# MAX30100_Adapter.net
KiCad netlist of a schematic drawn in EAGLE
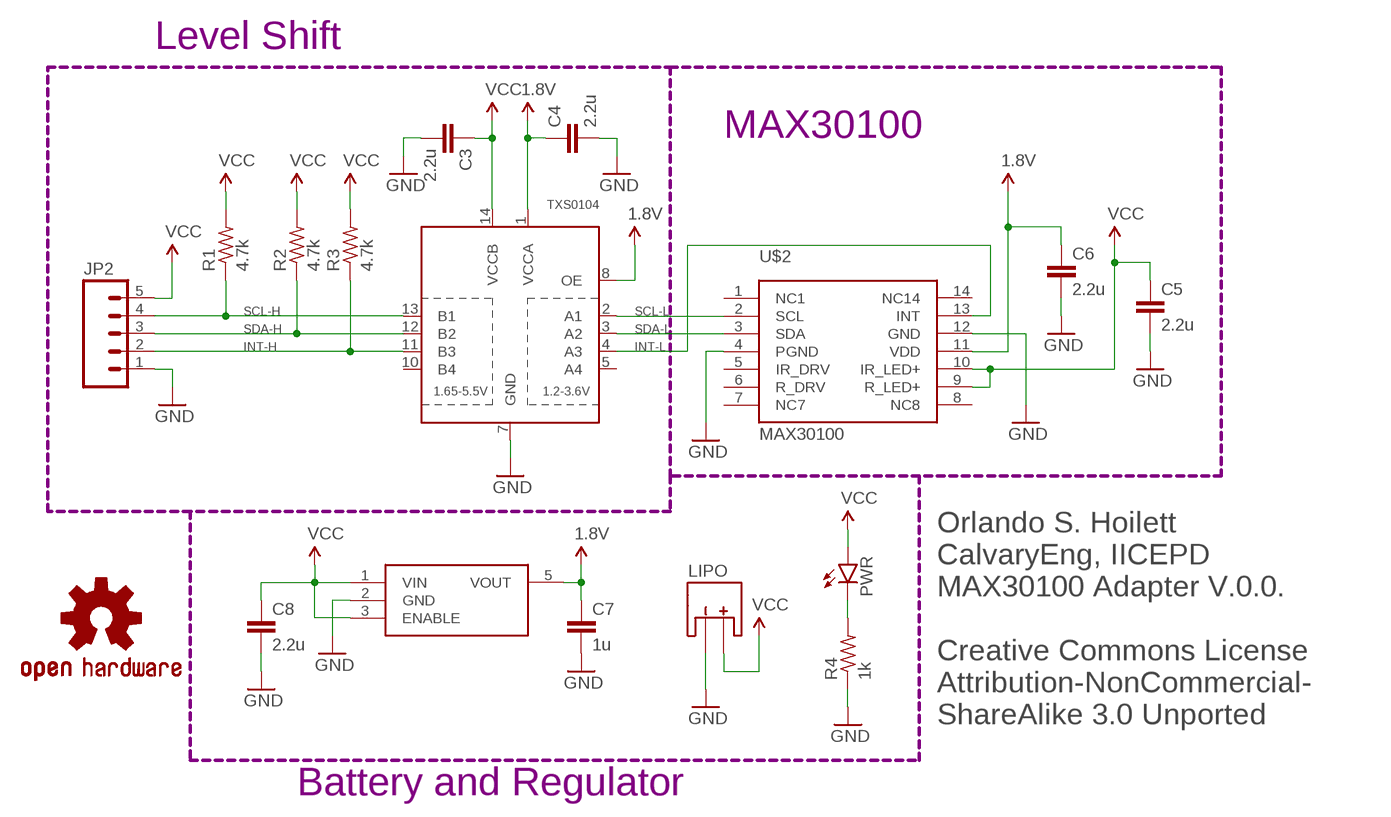
[diagram p0: schematic, sheet 1]

(export (version "E")
  (design (tool "Eeschema 10.0.6"))
  (components
    (comp (ref "C3")
      (value "2.2u")
      (footprint "eagle-import:C0402")
      (libsource (lib "eagle-import") (part "C-EUC0402"))
    )
    (comp (ref "C4")
      (value "2.2u")
      (footprint "eagle-import:C0402")
      (libsource (lib "eagle-import") (part "C-EUC0402"))
    )
    (comp (ref "C5")
      (value "2.2u")
      (footprint "eagle-import:C0402")
      (libsource (lib "eagle-import") (part "C-EUC0402"))
    )
    (comp (ref "C6")
      (value "2.2u")
      (footprint "eagle-import:C0402")
      (libsource (lib "eagle-import") (part "C-EUC0402"))
    )
    (comp (ref "C7")
      (value "1u")
      (footprint "eagle-import:C0402")
      (libsource (lib "eagle-import") (part "C-EUC0402"))
    )
    (comp (ref "C8")
      (value "2.2u")
      (footprint "eagle-import:C0402")
      (libsource (lib "eagle-import") (part "C-EUC0402"))
    )
    (comp (ref "JP2")
      (value "M05NO_SILK")
      (footprint "eagle-import:1X05_NO_SILK")
      (libsource (lib "eagle-import") (part "M05NO_SILK"))
    )
    (comp (ref "LDO")
      (value "MIC5504")
      (footprint "eagle-import:SOT23-5")
      (libsource (lib "eagle-import") (part "MIC5504"))
    )
    (comp (ref "LIPO")
      (value "JST-PTH")
      (footprint "eagle-import:JST-2-PTH-VERT")
      (libsource (lib "eagle-import") (part "JST-PTH"))
    )
    (comp (ref "LOGO1")
      (value "OSHW-LOGOS")
      (footprint "eagle-import:OSHW-LOGO-S")
      (libsource (lib "eagle-import") (part "OSHW-LOGOS"))
    )
    (comp (ref "PWR")
      (value "LED0603")
      (footprint "eagle-import:LED-0603")
      (libsource (lib "eagle-import") (part "LED0603"))
    )
    (comp (ref "R1")
      (value "4.7k")
      (footprint "eagle-import:R0402")
      (libsource (lib "eagle-import") (part "R-US_R0402"))
    )
    (comp (ref "R2")
      (value "4.7k")
      (footprint "eagle-import:R0402")
      (libsource (lib "eagle-import") (part "R-US_R0402"))
    )
    (comp (ref "R3")
      (value "4.7k")
      (footprint "eagle-import:R0402")
      (libsource (lib "eagle-import") (part "R-US_R0402"))
    )
    (comp (ref "R4")
      (value "1k")
      (footprint "eagle-import:R0402")
      (libsource (lib "eagle-import") (part "R-US_R0402"))
    )
    (comp (ref "TXS0104")
      (value "TXB0104PWR")
      (footprint "eagle-import:TSSOP14")
      (libsource (lib "eagle-import") (part "TXB0104PWR"))
    )
    (comp (ref "U$2")
      (value "MAX30100")
      (footprint "eagle-import:OESIP14")
      (libsource (lib "eagle-import") (part "MAX30100"))
    )
  )
  (nets
    (net (code "1") (name "/INT-H") (class "Default")
      (node (ref "JP2") (pin "2") (pinfunction "2_2") (pintype "passive"))
      (node (ref "R3") (pin "1") (pinfunction "1_1") (pintype "passive"))
      (node (ref "TXS0104") (pin "11") (pinfunction "B3_11") (pintype "bidirectional"))
    )
    (net (code "2") (name "/INT-L") (class "Default")
      (node (ref "TXS0104") (pin "4") (pinfunction "A3_4") (pintype "bidirectional"))
      (node (ref "U$2") (pin "13") (pinfunction "INT_13") (pintype "bidirectional"))
    )
    (net (code "3") (name "/SCL-H") (class "Default")
      (node (ref "JP2") (pin "4") (pinfunction "4_4") (pintype "passive"))
      (node (ref "R1") (pin "1") (pinfunction "1_1") (pintype "passive"))
      (node (ref "TXS0104") (pin "13") (pinfunction "B1_13") (pintype "bidirectional"))
    )
    (net (code "4") (name "/SCL-L") (class "Default")
      (node (ref "TXS0104") (pin "2") (pinfunction "A1_2") (pintype "bidirectional"))
      (node (ref "U$2") (pin "2") (pinfunction "SCL_2") (pintype "bidirectional"))
    )
    (net (code "5") (name "/SDA-H") (class "Default")
      (node (ref "JP2") (pin "3") (pinfunction "3_3") (pintype "passive"))
      (node (ref "R2") (pin "1") (pinfunction "1_1") (pintype "passive"))
      (node (ref "TXS0104") (pin "12") (pinfunction "B2_12") (pintype "bidirectional"))
    )
    (net (code "6") (name "/SDA-L") (class "Default")
      (node (ref "TXS0104") (pin "3") (pinfunction "A2_3") (pintype "bidirectional"))
      (node (ref "U$2") (pin "3") (pinfunction "SDA_3") (pintype "bidirectional"))
    )
    (net (code "7") (name "1.8V") (class "Default")
      (node (ref "C4") (pin "1") (pinfunction "1_1") (pintype "passive"))
      (node (ref "C6") (pin "1") (pinfunction "1_1") (pintype "passive"))
      (node (ref "C7") (pin "1") (pinfunction "1_1") (pintype "passive"))
      (node (ref "LDO") (pin "5") (pinfunction "VOUT_5") (pintype "bidirectional"))
      (node (ref "TXS0104") (pin "1") (pinfunction "VCCA_1") (pintype "bidirectional"))
      (node (ref "TXS0104") (pin "8") (pinfunction "OE_8") (pintype "bidirectional"))
      (node (ref "U$2") (pin "11") (pinfunction "VDD_11") (pintype "bidirectional"))
    )
    (net (code "8") (name "GND") (class "Default")
      (node (ref "C3") (pin "2") (pinfunction "2_2") (pintype "passive"))
      (node (ref "C4") (pin "2") (pinfunction "2_2") (pintype "passive"))
      (node (ref "C5") (pin "2") (pinfunction "2_2") (pintype "passive"))
      (node (ref "C6") (pin "2") (pinfunction "2_2") (pintype "passive"))
      (node (ref "C7") (pin "2") (pinfunction "2_2") (pintype "passive"))
      (node (ref "C8") (pin "2") (pinfunction "2_2") (pintype "passive"))
      (node (ref "JP2") (pin "1") (pinfunction "1_1") (pintype "passive"))
      (node (ref "LDO") (pin "2") (pinfunction "GND_2") (pintype "bidirectional"))
      (node (ref "LIPO") (pin "-") (pinfunction "-_-") (pintype "bidirectional"))
      (node (ref "R4") (pin "1") (pinfunction "1_1") (pintype "passive"))
      (node (ref "TXS0104") (pin "7") (pinfunction "GND_7") (pintype "bidirectional"))
      (node (ref "U$2") (pin "12") (pinfunction "GND_12") (pintype "bidirectional"))
      (node (ref "U$2") (pin "4") (pinfunction "PGND_4") (pintype "bidirectional"))
    )
    (net (code "9") (name "Net-(PWR-PadC)") (class "Default")
      (node (ref "PWR") (pin "C") (pinfunction "C_C") (pintype "passive"))
      (node (ref "R4") (pin "2") (pinfunction "2_2") (pintype "passive"))
    )
    (net (code "10") (name "VCC") (class "Default")
      (node (ref "C3") (pin "1") (pinfunction "1_1") (pintype "passive"))
      (node (ref "C5") (pin "1") (pinfunction "1_1") (pintype "passive"))
      (node (ref "C8") (pin "1") (pinfunction "1_1") (pintype "passive"))
      (node (ref "JP2") (pin "5") (pinfunction "5_5") (pintype "passive"))
      (node (ref "LDO") (pin "1") (pinfunction "VIN_1") (pintype "bidirectional"))
      (node (ref "LDO") (pin "3") (pinfunction "ENABLE_3") (pintype "bidirectional"))
      (node (ref "LIPO") (pin "+") (pinfunction "+_+") (pintype "bidirectional"))
      (node (ref "PWR") (pin "A") (pinfunction "A_A") (pintype "passive"))
      (node (ref "R1") (pin "2") (pinfunction "2_2") (pintype "passive"))
      (node (ref "R2") (pin "2") (pinfunction "2_2") (pintype "passive"))
      (node (ref "R3") (pin "2") (pinfunction "2_2") (pintype "passive"))
      (node (ref "TXS0104") (pin "14") (pinfunction "VCCB_14") (pintype "bidirectional"))
      (node (ref "U$2") (pin "10") (pinfunction "IR_LED+_10") (pintype "bidirectional"))
      (node (ref "U$2") (pin "9") (pinfunction "R_LED+_9") (pintype "bidirectional"))
    )
    (net (code "11") (name "unconnected-(TXS0104-A4-Pad5)") (class "Default")
      (node (ref "TXS0104") (pin "5") (pinfunction "A4_5") (pintype "bidirectional"))
    )
    (net (code "12") (name "unconnected-(TXS0104-B4-Pad10)") (class "Default")
      (node (ref "TXS0104") (pin "10") (pinfunction "B4_10") (pintype "bidirectional"))
    )
    (net (code "13") (name "unconnected-(U$2-IR_DRV-Pad5)") (class "Default")
      (node (ref "U$2") (pin "5") (pinfunction "IR_DRV_5") (pintype "bidirectional"))
    )
    (net (code "14") (name "unconnected-(U$2-NC1-Pad1)") (class "Default")
      (node (ref "U$2") (pin "1") (pinfunction "NC1_1") (pintype "bidirectional"))
    )
    (net (code "15") (name "unconnected-(U$2-NC7-Pad7)") (class "Default")
      (node (ref "U$2") (pin "7") (pinfunction "NC7_7") (pintype "bidirectional"))
    )
    (net (code "16") (name "unconnected-(U$2-NC8-Pad8)") (class "Default")
      (node (ref "U$2") (pin "8") (pinfunction "NC8_8") (pintype "bidirectional"))
    )
    (net (code "17") (name "unconnected-(U$2-NC14-Pad14)") (class "Default")
      (node (ref "U$2") (pin "14") (pinfunction "NC14_14") (pintype "bidirectional"))
    )
    (net (code "18") (name "unconnected-(U$2-R_DRV-Pad6)") (class "Default")
      (node (ref "U$2") (pin "6") (pinfunction "R_DRV_6") (pintype "bidirectional"))
    )
  )
)
